# m913b-breadboard.net
KiCad netlist of a schematic drawn in EAGLE
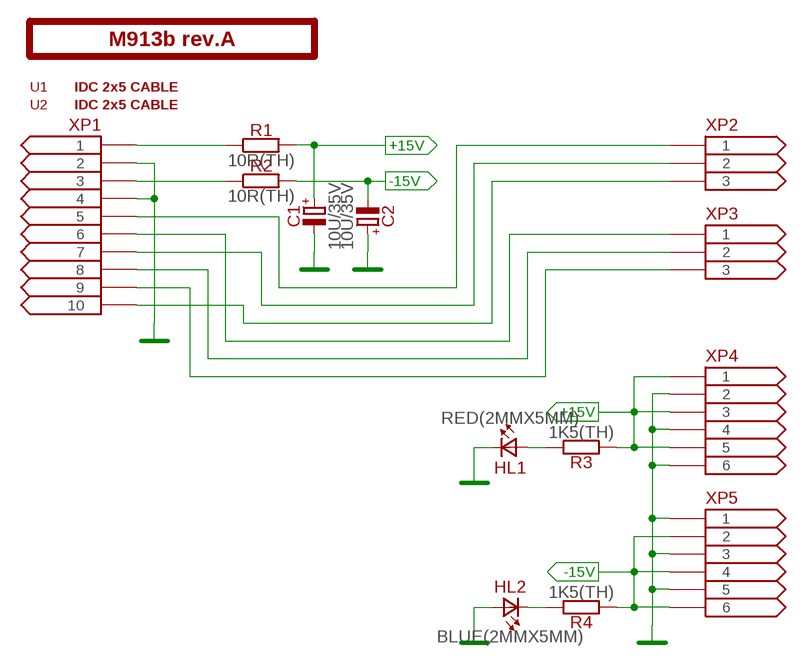
[diagram p0: schematic, sheet 1]

(export (version "E")
  (design (tool "Eeschema 10.0.6"))
  (components
    (comp (ref "C1")
      (value "10U/35V")
      (footprint "eagle-import:E2-5")
      (libsource (lib "eagle-import") (part "?10U/35V"))
    )
    (comp (ref "C2")
      (value "10U/35V")
      (footprint "eagle-import:E2-5")
      (libsource (lib "eagle-import") (part "?10U/35V"))
    )
    (comp (ref "HL1")
      (value "RED(2MMX5MM)")
      (footprint "eagle-import:LED2X5")
      (libsource (lib "eagle-import") (part "?(2MMX5MM)RED"))
    )
    (comp (ref "HL2")
      (value "BLUE(2MMX5MM)")
      (footprint "eagle-import:LED2X5")
      (libsource (lib "eagle-import") (part "?(2MMX5MM)BLUE"))
    )
    (comp (ref "PCB1")
      (value "M913b rev.A")
      (footprint "eagle-import:EMPTY")
      (libsource (lib "eagle-import") (part "GENERIC"))
    )
    (comp (ref "R1")
      (value "10R(TH)")
      (footprint "eagle-import:R-0207_10")
      (libsource (lib "eagle-import") (part "?10R(TH)"))
    )
    (comp (ref "R2")
      (value "10R(TH)")
      (footprint "eagle-import:R-0207_10")
      (libsource (lib "eagle-import") (part "?10R(TH)"))
    )
    (comp (ref "R3")
      (value "1K5(TH)")
      (footprint "eagle-import:R-0207_10")
      (libsource (lib "eagle-import") (part "?1K5(TH)"))
    )
    (comp (ref "R4")
      (value "1K5(TH)")
      (footprint "eagle-import:R-0207_10")
      (libsource (lib "eagle-import") (part "?1K5(TH)"))
    )
    (comp (ref "U1")
      (value "IDC 2x5 CABLE")
      (footprint "eagle-import:EMPTY")
      (libsource (lib "eagle-import") (part "OTHER"))
    )
    (comp (ref "U2")
      (value "IDC 2x5 CABLE")
      (footprint "eagle-import:EMPTY")
      (libsource (lib "eagle-import") (part "OTHER"))
    )
    (comp (ref "XP1")
      (value "CONN-10-IDC")
      (footprint "eagle-import:ML10")
      (libsource (lib "eagle-import") (part "CONN-10-?IDC"))
    )
    (comp (ref "XP2")
      (value "CONN-3-NORMAL")
      (footprint "eagle-import:MA03-1")
      (libsource (lib "eagle-import") (part "CONN-3-?NORMAL"))
    )
    (comp (ref "XP3")
      (value "CONN-3-NORMAL")
      (footprint "eagle-import:MA03-1")
      (libsource (lib "eagle-import") (part "CONN-3-?NORMAL"))
    )
    (comp (ref "XP4")
      (value "CONN-6-NORMAL")
      (footprint "eagle-import:MA03-2")
      (libsource (lib "eagle-import") (part "CONN-6-?NORMAL"))
    )
    (comp (ref "XP5")
      (value "CONN-6-NORMAL")
      (footprint "eagle-import:MA03-2")
      (libsource (lib "eagle-import") (part "CONN-6-?NORMAL"))
    )
  )
  (nets
    (net (code "1") (name "+15V") (class "Default")
      (node (ref "C1") (pin "+") (pinfunction "+_+") (pintype "passive"))
      (node (ref "R1") (pin "2") (pinfunction "2_2") (pintype "passive"))
      (node (ref "R3") (pin "1") (pinfunction "1_1") (pintype "passive"))
      (node (ref "XP4") (pin "1") (pinfunction "1_1") (pintype "passive"))
      (node (ref "XP4") (pin "3") (pinfunction "3_3") (pintype "passive"))
      (node (ref "XP4") (pin "5") (pinfunction "5_5") (pintype "passive"))
    )
    (net (code "2") (name "-15V") (class "Default")
      (node (ref "C2") (pin "-") (pinfunction "-_-") (pintype "passive"))
      (node (ref "R2") (pin "2") (pinfunction "2_2") (pintype "passive"))
      (node (ref "R4") (pin "1") (pinfunction "1_1") (pintype "passive"))
      (node (ref "XP5") (pin "2") (pinfunction "2_2") (pintype "passive"))
      (node (ref "XP5") (pin "4") (pinfunction "4_4") (pintype "passive"))
      (node (ref "XP5") (pin "6") (pinfunction "6_6") (pintype "passive"))
    )
    (net (code "3") (name "GND") (class "Default")
      (node (ref "C1") (pin "-") (pinfunction "-_-") (pintype "passive"))
      (node (ref "C2") (pin "+") (pinfunction "+_+") (pintype "passive"))
      (node (ref "HL1") (pin "K") (pinfunction "C_K") (pintype "passive"))
      (node (ref "HL2") (pin "A") (pinfunction "A_A") (pintype "passive"))
      (node (ref "XP1") (pin "2") (pinfunction "2_2") (pintype "passive"))
      (node (ref "XP1") (pin "4") (pinfunction "4_4") (pintype "passive"))
      (node (ref "XP4") (pin "2") (pinfunction "2_2") (pintype "passive"))
      (node (ref "XP4") (pin "4") (pinfunction "4_4") (pintype "passive"))
      (node (ref "XP4") (pin "6") (pinfunction "6_6") (pintype "passive"))
      (node (ref "XP5") (pin "1") (pinfunction "1_1") (pintype "passive"))
      (node (ref "XP5") (pin "3") (pinfunction "3_3") (pintype "passive"))
      (node (ref "XP5") (pin "5") (pinfunction "5_5") (pintype "passive"))
    )
    (net (code "4") (name "Net-(HL1-PadA)") (class "Default")
      (node (ref "HL1") (pin "A") (pinfunction "A_A") (pintype "passive"))
      (node (ref "R3") (pin "2") (pinfunction "2_2") (pintype "passive"))
    )
    (net (code "5") (name "Net-(HL2-C)") (class "Default")
      (node (ref "HL2") (pin "K") (pinfunction "C_K") (pintype "passive"))
      (node (ref "R4") (pin "2") (pinfunction "2_2") (pintype "passive"))
    )
    (net (code "6") (name "Net-(R1-Pad1)") (class "Default")
      (node (ref "R1") (pin "1") (pinfunction "1_1") (pintype "passive"))
      (node (ref "XP1") (pin "1") (pinfunction "1_1") (pintype "passive"))
    )
    (net (code "7") (name "Net-(R2-Pad1)") (class "Default")
      (node (ref "R2") (pin "1") (pinfunction "1_1") (pintype "passive"))
      (node (ref "XP1") (pin "3") (pinfunction "3_3") (pintype "passive"))
    )
    (net (code "8") (name "Net-(XP1-Pad5)") (class "Default")
      (node (ref "XP1") (pin "5") (pinfunction "5_5") (pintype "passive"))
      (node (ref "XP2") (pin "1") (pinfunction "1_1") (pintype "passive"))
    )
    (net (code "9") (name "Net-(XP1-Pad6)") (class "Default")
      (node (ref "XP1") (pin "6") (pinfunction "6_6") (pintype "passive"))
      (node (ref "XP3") (pin "1") (pinfunction "1_1") (pintype "passive"))
    )
    (net (code "10") (name "Net-(XP1-Pad7)") (class "Default")
      (node (ref "XP1") (pin "7") (pinfunction "7_7") (pintype "passive"))
      (node (ref "XP2") (pin "2") (pinfunction "2_2") (pintype "passive"))
    )
    (net (code "11") (name "Net-(XP1-Pad8)") (class "Default")
      (node (ref "XP1") (pin "8") (pinfunction "8_8") (pintype "passive"))
      (node (ref "XP3") (pin "2") (pinfunction "2_2") (pintype "passive"))
    )
    (net (code "12") (name "Net-(XP1-Pad9)") (class "Default")
      (node (ref "XP1") (pin "9") (pinfunction "9_9") (pintype "passive"))
      (node (ref "XP3") (pin "3") (pinfunction "3_3") (pintype "passive"))
    )
    (net (code "13") (name "Net-(XP1-Pad10)") (class "Default")
      (node (ref "XP1") (pin "10") (pinfunction "10_10") (pintype "passive"))
      (node (ref "XP2") (pin "3") (pinfunction "3_3") (pintype "passive"))
    )
  )
)
